# Plugs.net
KiCad netlist of a schematic drawn in Altium Designer
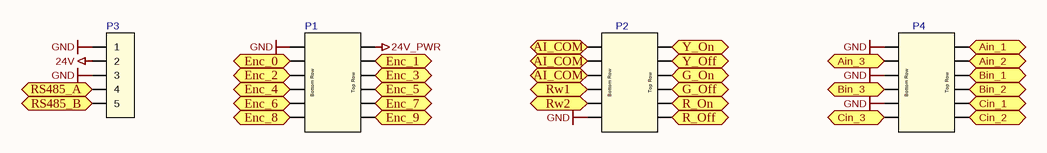
[diagram p0: Plugs.SchDoc]

(export (version "E")
  (design (tool "Eeschema 10.0.6"))
  (components
    (comp (ref "P1")
      (value "Conncector 6x2")
      (footprint "Connector 6x2")
      (description "MCD 1,5/6-G1-3,81 PCB Connector")
      (libsource (lib "levin") (part "Conncector 6x2"))
    )
    (comp (ref "P2")
      (value "Conncector 6x2")
      (footprint "Connector 6x2")
      (description "MCD 1,5/6-G1-3,81 PCB Connector")
      (libsource (lib "levin") (part "Conncector 6x2"))
    )
    (comp (ref "P3")
      (value "Conncector X2X")
      (footprint "Connector X2X")
      (description "EMSTBA 2,5/ 5-G-5,08 PCB Connector")
      (libsource (lib "levin") (part "Connector X2X"))
    )
    (comp (ref "P4")
      (value "Conncector 6x2")
      (footprint "Connector 6x2")
      (description "MCD 1,5/6-G1-3,81 PCB Connector")
      (libsource (lib "levin") (part "Conncector 6x2"))
    )
  )
  (nets
    (net (code "1") (name "/AI_COM") (class "Default")
      (node (ref "P2") (pin "1") (pinfunction "1_1") (pintype "passive"))
      (node (ref "P2") (pin "3") (pinfunction "3_3") (pintype "passive"))
      (node (ref "P2") (pin "5") (pinfunction "5_5") (pintype "passive"))
    )
    (net (code "2") (name "/Ain_1") (class "Default")
      (node (ref "P4") (pin "2") (pinfunction "2_2") (pintype "passive"))
    )
    (net (code "3") (name "/Ain_2") (class "Default")
      (node (ref "P4") (pin "4") (pinfunction "4_4") (pintype "passive"))
    )
    (net (code "4") (name "/Ain_3") (class "Default")
      (node (ref "P4") (pin "3") (pinfunction "3_3") (pintype "passive"))
    )
    (net (code "5") (name "/Bin_1") (class "Default")
      (node (ref "P4") (pin "6") (pinfunction "6_6") (pintype "passive"))
    )
    (net (code "6") (name "/Bin_2") (class "Default")
      (node (ref "P4") (pin "8") (pinfunction "8_8") (pintype "passive"))
    )
    (net (code "7") (name "/Bin_3") (class "Default")
      (node (ref "P4") (pin "7") (pinfunction "7_7") (pintype "passive"))
    )
    (net (code "8") (name "/Cin_1") (class "Default")
      (node (ref "P4") (pin "10") (pinfunction "10_10") (pintype "passive"))
    )
    (net (code "9") (name "/Cin_2") (class "Default")
      (node (ref "P4") (pin "12") (pinfunction "12_12") (pintype "passive"))
    )
    (net (code "10") (name "/Cin_3") (class "Default")
      (node (ref "P4") (pin "11") (pinfunction "11_11") (pintype "passive"))
    )
    (net (code "11") (name "/Enc_0") (class "Default")
      (node (ref "P1") (pin "3") (pinfunction "3_3") (pintype "passive"))
    )
    (net (code "12") (name "/Enc_1") (class "Default")
      (node (ref "P1") (pin "4") (pinfunction "4_4") (pintype "passive"))
    )
    (net (code "13") (name "/Enc_2") (class "Default")
      (node (ref "P1") (pin "5") (pinfunction "5_5") (pintype "passive"))
    )
    (net (code "14") (name "/Enc_3") (class "Default")
      (node (ref "P1") (pin "6") (pinfunction "6_6") (pintype "passive"))
    )
    (net (code "15") (name "/Enc_4") (class "Default")
      (node (ref "P1") (pin "7") (pinfunction "7_7") (pintype "passive"))
    )
    (net (code "16") (name "/Enc_5") (class "Default")
      (node (ref "P1") (pin "8") (pinfunction "8_8") (pintype "passive"))
    )
    (net (code "17") (name "/Enc_6") (class "Default")
      (node (ref "P1") (pin "9") (pinfunction "9_9") (pintype "passive"))
    )
    (net (code "18") (name "/Enc_7") (class "Default")
      (node (ref "P1") (pin "10") (pinfunction "10_10") (pintype "passive"))
    )
    (net (code "19") (name "/Enc_8") (class "Default")
      (node (ref "P1") (pin "11") (pinfunction "11_11") (pintype "passive"))
    )
    (net (code "20") (name "/Enc_9") (class "Default")
      (node (ref "P1") (pin "12") (pinfunction "12_12") (pintype "passive"))
    )
    (net (code "21") (name "/G_Off") (class "Default")
      (node (ref "P2") (pin "8") (pinfunction "8_8") (pintype "passive"))
    )
    (net (code "22") (name "/G_On") (class "Default")
      (node (ref "P2") (pin "6") (pinfunction "6_6") (pintype "passive"))
    )
    (net (code "23") (name "/RS485_A") (class "Default")
      (node (ref "P3") (pin "4") (pinfunction "4_4") (pintype "passive"))
    )
    (net (code "24") (name "/RS485_B") (class "Default")
      (node (ref "P3") (pin "5") (pinfunction "5_5") (pintype "passive"))
    )
    (net (code "25") (name "/R_Off") (class "Default")
      (node (ref "P2") (pin "12") (pinfunction "12_12") (pintype "passive"))
    )
    (net (code "26") (name "/R_On") (class "Default")
      (node (ref "P2") (pin "10") (pinfunction "10_10") (pintype "passive"))
    )
    (net (code "27") (name "/Rw1") (class "Default")
      (node (ref "P2") (pin "7") (pinfunction "7_7") (pintype "passive"))
    )
    (net (code "28") (name "/Rw2") (class "Default")
      (node (ref "P2") (pin "9") (pinfunction "9_9") (pintype "passive"))
    )
    (net (code "29") (name "/Y_Off") (class "Default")
      (node (ref "P2") (pin "4") (pinfunction "4_4") (pintype "passive"))
    )
    (net (code "30") (name "/Y_On") (class "Default")
      (node (ref "P2") (pin "2") (pinfunction "2_2") (pintype "passive"))
    )
    (net (code "31") (name "24V") (class "Default")
      (node (ref "P3") (pin "2") (pinfunction "2_2") (pintype "passive"))
    )
    (net (code "32") (name "24V_PWR") (class "Default")
      (node (ref "P1") (pin "2") (pinfunction "2_2") (pintype "passive"))
    )
    (net (code "33") (name "GND") (class "Default")
      (node (ref "P1") (pin "1") (pinfunction "1_1") (pintype "passive"))
      (node (ref "P2") (pin "11") (pinfunction "11_11") (pintype "passive"))
      (node (ref "P3") (pin "1") (pinfunction "1_1") (pintype "passive"))
      (node (ref "P3") (pin "3") (pinfunction "3_3") (pintype "passive"))
      (node (ref "P4") (pin "1") (pinfunction "1_1") (pintype "passive"))
      (node (ref "P4") (pin "5") (pinfunction "5_5") (pintype "passive"))
      (node (ref "P4") (pin "9") (pinfunction "9_9") (pintype "passive"))
    )
  )
)
